# Sensor_Base_Schematic.net
KiCad netlist of a schematic drawn in Altium Designer
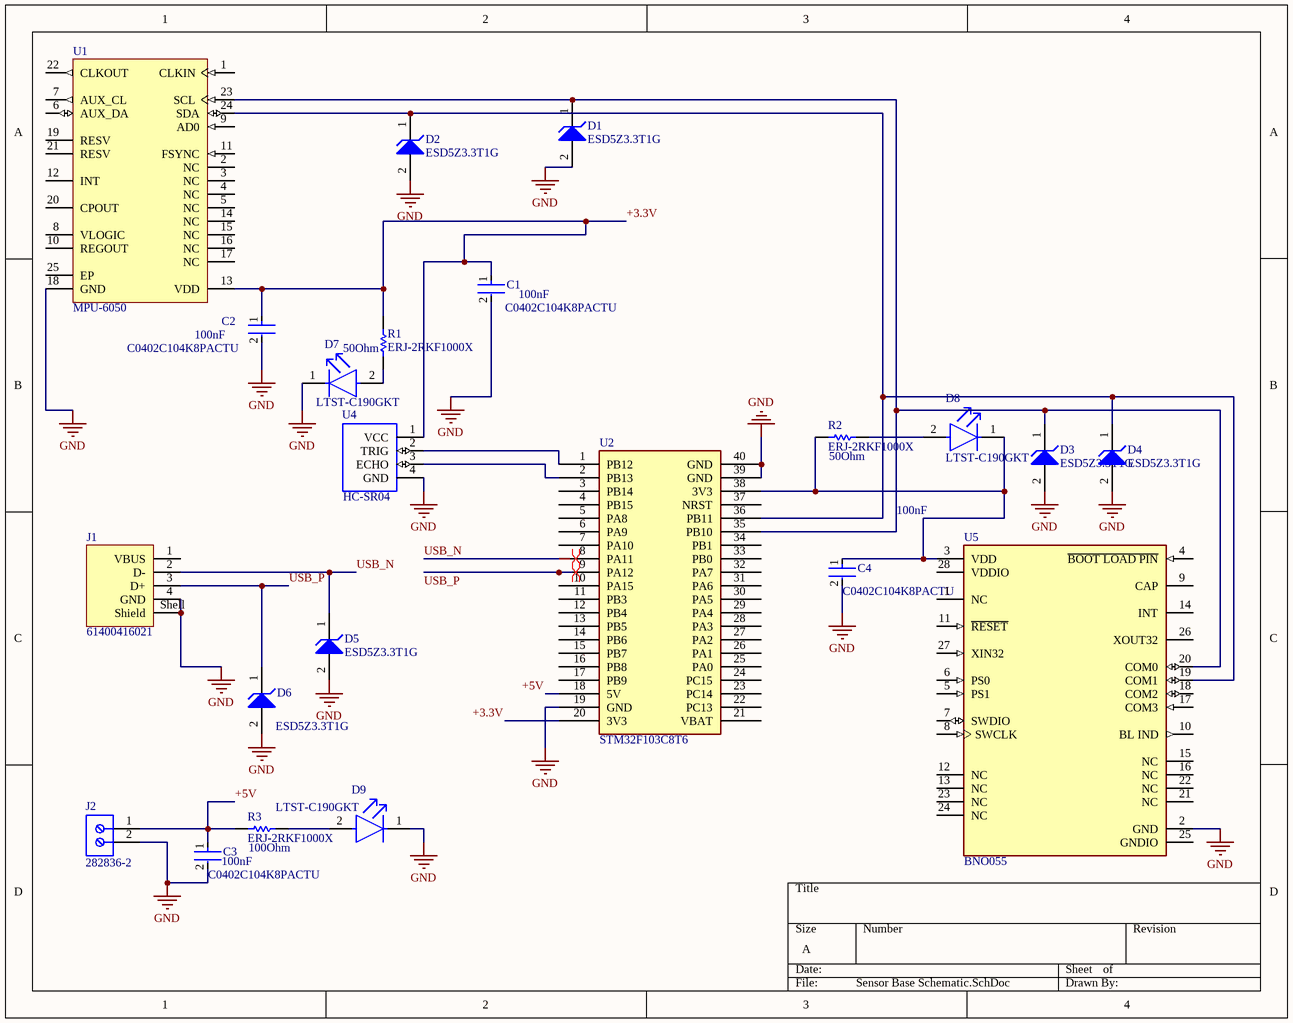
[diagram p0: Sensor Base Schematic.SchDoc]

(export (version "E")
  (design (tool "Eeschema 10.0.6"))
  (components
    (comp (ref "C1")
      (value "C0402C104K8PACTU")
      (footprint "FP-C0402-BB-MFG")
      (description "CAP CER 0.1UF 10V X5R 0402")
      (fields (field (name "MANUFACTURER") "Kemet") (field (name "TOLERANCE") "0.1"))
      (libsource (lib "Altium Content Vault") (part "b4654b650e69147ec39a6b967a45e02"))
    )
    (comp (ref "C2")
      (value "C0402C104K8PACTU")
      (footprint "FP-C0402-BB-MFG")
      (description "CAP CER 0.1UF 10V X5R 0402")
      (fields (field (name "MANUFACTURER") "Kemet") (field (name "TOLERANCE") "0.1"))
      (libsource (lib "Altium Content Vault") (part "b4654b650e69147ec39a6b967a45e02"))
    )
    (comp (ref "C3")
      (value "C0402C104K8PACTU")
      (footprint "FP-C0402-BB-MFG")
      (description "CAP CER 0.1UF 10V X5R 0402")
      (fields (field (name "MANUFACTURER") "Kemet") (field (name "TOLERANCE") "0.1"))
      (libsource (lib "Altium Content Vault") (part "b4654b650e69147ec39a6b967a45e02"))
    )
    (comp (ref "C4")
      (value "C0402C104K8PACTU")
      (footprint "FP-C0402-BB-MFG")
      (description "CAP CER 0.1UF 10V X5R 0402")
      (fields (field (name "MANUFACTURER") "Kemet") (field (name "TOLERANCE") "0.1"))
      (libsource (lib "Altium Content Vault") (part "b4654b650e69147ec39a6b967a45e02"))
    )
    (comp (ref "D1")
      (value "ESD5Z3.3T1G")
      (footprint "ONSC-SOD-523-2-502-01_V")
      (fields (field (name "MANUFACTURER") "On Semiconductor"))
      (libsource (lib "Altium Content Vault") (part "ONSC-K1A2-2"))
    )
    (comp (ref "D2")
      (value "ESD5Z3.3T1G")
      (footprint "ONSC-SOD-523-2-502-01_V")
      (fields (field (name "MANUFACTURER") "On Semiconductor"))
      (libsource (lib "Altium Content Vault") (part "ONSC-K1A2-2"))
    )
    (comp (ref "D3")
      (value "ESD5Z3.3T1G")
      (footprint "ONSC-SOD-523-2-502-01_V")
      (fields (field (name "MANUFACTURER") "On Semiconductor"))
      (libsource (lib "Altium Content Vault") (part "ONSC-K1A2-2"))
    )
    (comp (ref "D4")
      (value "ESD5Z3.3T1G")
      (footprint "ONSC-SOD-523-2-502-01_V")
      (fields (field (name "MANUFACTURER") "On Semiconductor"))
      (libsource (lib "Altium Content Vault") (part "ONSC-K1A2-2"))
    )
    (comp (ref "D5")
      (value "ESD5Z3.3T1G")
      (footprint "ONSC-SOD-523-2-502-01_V")
      (fields (field (name "MANUFACTURER") "On Semiconductor"))
      (libsource (lib "Altium Content Vault") (part "ONSC-K1A2-2"))
    )
    (comp (ref "D6")
      (value "ESD5Z3.3T1G")
      (footprint "ONSC-SOD-523-2-502-01_V")
      (fields (field (name "MANUFACTURER") "On Semiconductor"))
      (libsource (lib "Altium Content Vault") (part "ONSC-K1A2-2"))
    )
    (comp (ref "D7")
      (value "LTST-C190GKT")
      (footprint "FP-LTST-C190GKT-MFG")
      (description "LED GREEN CLEAR CHIP SMD")
      (fields (field (name "VOLTAGE") "2V"))
      (libsource (lib "Altium Content Vault") (part "8706943c75ba83719d021d2fdc84c58"))
    )
    (comp (ref "D8")
      (value "LTST-C190GKT")
      (footprint "FP-LTST-C190GKT-MFG")
      (description "LED GREEN CLEAR CHIP SMD")
      (fields (field (name "VOLTAGE") "2V"))
      (libsource (lib "Altium Content Vault") (part "8706943c75ba83719d021d2fdc84c58"))
    )
    (comp (ref "D9")
      (value "LTST-C190GKT")
      (footprint "FP-LTST-C190GKT-MFG")
      (description "LED GREEN CLEAR CHIP SMD")
      (fields (field (name "VOLTAGE") "2V"))
      (libsource (lib "Altium Content Vault") (part "8706943c75ba83719d021d2fdc84c58"))
    )
    (comp (ref "J1")
      (value "61400416021")
      (footprint "61400416021")
      (libsource (lib "Altium Content Vault") (part "USB 2.0_Type A_Receptacle_1 Port"))
    )
    (comp (ref "J2")
      (value "282836-2")
      (footprint "TECO-282836-2_V")
      (description "Female Header, Pitch 5 mm, 1 x 2 Position, Height 10 mm, Tail Length 3.5 mm, Rohs, Bulk")
      (fields (field (name "VOLTAGE") "300V") (field (name "MANUFACTURER") "TE Connectivity"))
      (libsource (lib "Altium Content Vault") (part "CN-1P-F-TB2"))
    )
    (comp (ref "R1")
      (value "ERJ-2RKF1000X")
      (footprint "RESC1005X40X25LL05T05")
      (description "Chip Resistor, 100 Ohm, +/- 1%, 100 mW, -55 to 155 degC, 0402 (1005 Metric), RoHS, Tape and Reel")
      (fields (field (name "MANUFACTURER") "Basic Passives") (field (name "TOLERANCE") "1%"))
      (libsource (lib "Altium Content Vault") (part "RES-2"))
    )
    (comp (ref "R2")
      (value "ERJ-2RKF1000X")
      (footprint "RESC1005X40X25LL05T05")
      (description "Chip Resistor, 100 Ohm, +/- 1%, 100 mW, -55 to 155 degC, 0402 (1005 Metric), RoHS, Tape and Reel")
      (fields (field (name "MANUFACTURER") "Basic Passives") (field (name "TOLERANCE") "1%"))
      (libsource (lib "Altium Content Vault") (part "RES-2"))
    )
    (comp (ref "R3")
      (value "ERJ-2RKF1000X")
      (footprint "RESC1005X40X25LL05T05")
      (description "Chip Resistor, 100 Ohm, +/- 1%, 100 mW, -55 to 155 degC, 0402 (1005 Metric), RoHS, Tape and Reel")
      (fields (field (name "MANUFACTURER") "Basic Passives") (field (name "TOLERANCE") "1%"))
      (libsource (lib "Altium Content Vault") (part "RES-2"))
    )
    (comp (ref "U1")
      (value "MPU-6050")
      (footprint "IS-QFN-24_V")
      (fields (field (name "MANUFACTURER") "InvenSense"))
      (libsource (lib "Altium Content Vault") (part "IS-MPU-6050-QFN-24"))
    )
    (comp (ref "U2")
      (value "STM32F103C8T6")
      (footprint "Stm32 BluePill")
      (description "Designed By @Alixahedi")
      (libsource (lib "Stm32 Blue Pill") (part "BluePill"))
    )
    (comp (ref "U4")
      (value "HC-SR04")
      (footprint "XCVR_HC-SR04")
      (description "Ultrasonic Sensor Module")
      (libsource (lib "HC-SR04") (part "HC-SR04"))
    )
    (comp (ref "U5")
      (value "BNO055")
      (footprint "FP-BNO055-MFG")
      (description "IMU ACCEL/GYRO/MAG I2C 28LGA")
      (libsource (lib "Altium Content Vault") (part "ba837af00a0b6167256f888b31462b1"))
    )
  )
  (nets
    (net (code "1") (name "/+3.3V") (class "Default")
      (node (ref "C1") (pin "1") (pinfunction "1_1") (pintype "passive"))
      (node (ref "C2") (pin "1") (pinfunction "1_1") (pintype "passive"))
      (node (ref "R1") (pin "2") (pinfunction "2_2") (pintype "passive"))
      (node (ref "U1") (pin "13") (pinfunction "VDD_13") (pintype "power_in"))
      (node (ref "U2") (pin "20") (pinfunction "3V3_20") (pintype "passive"))
      (node (ref "U4") (pin "1") (pinfunction "VCC_1") (pintype "power_in"))
    )
    (net (code "2") (name "/+5V") (class "Default")
      (node (ref "C3") (pin "1") (pinfunction "1_1") (pintype "passive"))
      (node (ref "J2") (pin "1") (pinfunction "1_1") (pintype "passive"))
      (node (ref "R3") (pin "1") (pinfunction "1_1") (pintype "passive"))
      (node (ref "U2") (pin "18") (pinfunction "5V_18") (pintype "passive"))
    )
    (net (code "3") (name "/USB_N") (class "Default")
      (node (ref "D5") (pin "1") (pinfunction "K_1") (pintype "passive"))
      (node (ref "J1") (pin "2") (pinfunction "D-_2") (pintype "passive"))
      (node (ref "U2") (pin "8") (pinfunction "PA11_8") (pintype "passive"))
    )
    (net (code "4") (name "/USB_P") (class "Default")
      (node (ref "D6") (pin "1") (pinfunction "K_1") (pintype "passive"))
      (node (ref "J1") (pin "3") (pinfunction "D+_3") (pintype "passive"))
      (node (ref "U2") (pin "9") (pinfunction "PA12_9") (pintype "passive"))
    )
    (net (code "5") (name "GND") (class "Default")
      (node (ref "C1") (pin "2") (pinfunction "2_2") (pintype "passive"))
      (node (ref "C2") (pin "2") (pinfunction "2_2") (pintype "passive"))
      (node (ref "C3") (pin "2") (pinfunction "2_2") (pintype "passive"))
      (node (ref "C4") (pin "2") (pinfunction "2_2") (pintype "passive"))
      (node (ref "D1") (pin "2") (pinfunction "A_2") (pintype "passive"))
      (node (ref "D2") (pin "2") (pinfunction "A_2") (pintype "passive"))
      (node (ref "D3") (pin "2") (pinfunction "A_2") (pintype "passive"))
      (node (ref "D4") (pin "2") (pinfunction "A_2") (pintype "passive"))
      (node (ref "D5") (pin "2") (pinfunction "A_2") (pintype "passive"))
      (node (ref "D6") (pin "2") (pinfunction "A_2") (pintype "passive"))
      (node (ref "D7") (pin "1") (pinfunction "C_1") (pintype "passive"))
      (node (ref "D9") (pin "1") (pinfunction "C_1") (pintype "passive"))
      (node (ref "J1") (pin "4") (pinfunction "GND_4") (pintype "passive"))
      (node (ref "J1") (pin "Shell") (pinfunction "Shield_Shell") (pintype "passive"))
      (node (ref "J2") (pin "2") (pinfunction "2_2") (pintype "passive"))
      (node (ref "U1") (pin "18") (pinfunction "GND_18") (pintype "power_in"))
      (node (ref "U2") (pin "19") (pinfunction "GND_19") (pintype "passive"))
      (node (ref "U2") (pin "39") (pinfunction "GND_39") (pintype "passive"))
      (node (ref "U2") (pin "40") (pinfunction "GND_40") (pintype "passive"))
      (node (ref "U4") (pin "4") (pinfunction "GND_4") (pintype "power_in"))
      (node (ref "U5") (pin "2") (pinfunction "GND_2") (pintype "power_in"))
    )
    (net (code "6") (name "Net-(D1-K)") (class "Default")
      (node (ref "D1") (pin "1") (pinfunction "K_1") (pintype "passive"))
      (node (ref "D3") (pin "1") (pinfunction "K_1") (pintype "passive"))
      (node (ref "U1") (pin "23") (pinfunction "SCL_23") (pintype "input"))
      (node (ref "U2") (pin "35") (pinfunction "PB10_35") (pintype "passive"))
      (node (ref "U5") (pin "20") (pinfunction "COM0_20") (pintype "bidirectional"))
    )
    (net (code "7") (name "Net-(D2-K)") (class "Default")
      (node (ref "D2") (pin "1") (pinfunction "K_1") (pintype "passive"))
      (node (ref "D4") (pin "1") (pinfunction "K_1") (pintype "passive"))
      (node (ref "U1") (pin "24") (pinfunction "SDA_24") (pintype "bidirectional"))
      (node (ref "U2") (pin "36") (pinfunction "PB11_36") (pintype "passive"))
      (node (ref "U5") (pin "19") (pinfunction "COM1_19") (pintype "bidirectional"))
    )
    (net (code "8") (name "Net-(D7-A)") (class "Default")
      (node (ref "D7") (pin "2") (pinfunction "A_2") (pintype "passive"))
      (node (ref "R1") (pin "1") (pinfunction "1_1") (pintype "passive"))
    )
    (net (code "9") (name "Net-(D8-A)") (class "Default")
      (node (ref "D8") (pin "2") (pinfunction "A_2") (pintype "passive"))
      (node (ref "R2") (pin "2") (pinfunction "2_2") (pintype "passive"))
    )
    (net (code "10") (name "Net-(D8-C)") (class "Default")
      (node (ref "C4") (pin "1") (pinfunction "1_1") (pintype "passive"))
      (node (ref "D8") (pin "1") (pinfunction "C_1") (pintype "passive"))
      (node (ref "R2") (pin "1") (pinfunction "1_1") (pintype "passive"))
      (node (ref "U2") (pin "38") (pinfunction "3V3_38") (pintype "passive"))
      (node (ref "U5") (pin "3") (pinfunction "VDD_3") (pintype "power_in"))
    )
    (net (code "11") (name "Net-(D9-A)") (class "Default")
      (node (ref "D9") (pin "2") (pinfunction "A_2") (pintype "passive"))
      (node (ref "R3") (pin "2") (pinfunction "2_2") (pintype "passive"))
    )
    (net (code "12") (name "Net-(U2-PB12)") (class "Default")
      (node (ref "U2") (pin "1") (pinfunction "PB12_1") (pintype "passive"))
      (node (ref "U4") (pin "2") (pinfunction "TRIG_2") (pintype "bidirectional"))
    )
    (net (code "13") (name "Net-(U2-PB13)") (class "Default")
      (node (ref "U2") (pin "2") (pinfunction "PB13_2") (pintype "passive"))
      (node (ref "U4") (pin "3") (pinfunction "ECHO_3") (pintype "bidirectional"))
    )
    (net (code "14") (name "unconnected-(J1-VBUS-Pad1)") (class "Default")
      (node (ref "J1") (pin "1") (pinfunction "VBUS_1") (pintype "passive"))
    )
    (net (code "15") (name "unconnected-(U1-AD0-Pad9)") (class "Default")
      (node (ref "U1") (pin "9") (pinfunction "AD0_9") (pintype "input"))
    )
    (net (code "16") (name "unconnected-(U1-AUX_CL-Pad7)") (class "Default")
      (node (ref "U1") (pin "7") (pinfunction "AUX_CL_7") (pintype "output"))
    )
    (net (code "17") (name "unconnected-(U1-AUX_DA-Pad6)") (class "Default")
      (node (ref "U1") (pin "6") (pinfunction "AUX_DA_6") (pintype "bidirectional"))
    )
    (net (code "18") (name "unconnected-(U1-CLKIN-Pad1)") (class "Default")
      (node (ref "U1") (pin "1") (pinfunction "CLKIN_1") (pintype "input"))
    )
    (net (code "19") (name "unconnected-(U1-CLKOUT-Pad22)") (class "Default")
      (node (ref "U1") (pin "22") (pinfunction "CLKOUT_22") (pintype "output"))
    )
    (net (code "20") (name "unconnected-(U1-CPOUT-Pad20)") (class "Default")
      (node (ref "U1") (pin "20") (pinfunction "CPOUT_20") (pintype "passive"))
    )
    (net (code "21") (name "unconnected-(U1-EP-Pad25)") (class "Default")
      (node (ref "U1") (pin "25") (pinfunction "EP_25") (pintype "power_in"))
    )
    (net (code "22") (name "unconnected-(U1-FSYNC-Pad11)") (class "Default")
      (node (ref "U1") (pin "11") (pinfunction "FSYNC_11") (pintype "input"))
    )
    (net (code "23") (name "unconnected-(U1-INT-Pad12)") (class "Default")
      (node (ref "U1") (pin "12") (pinfunction "INT_12") (pintype "open_collector"))
    )
    (net (code "24") (name "unconnected-(U1-NC-Pad2)") (class "Default")
      (node (ref "U1") (pin "2") (pinfunction "NC_2") (pintype "passive"))
    )
    (net (code "25") (name "unconnected-(U1-NC-Pad3)") (class "Default")
      (node (ref "U1") (pin "3") (pinfunction "NC_3") (pintype "passive"))
    )
    (net (code "26") (name "unconnected-(U1-NC-Pad4)") (class "Default")
      (node (ref "U1") (pin "4") (pinfunction "NC_4") (pintype "passive"))
    )
    (net (code "27") (name "unconnected-(U1-NC-Pad5)") (class "Default")
      (node (ref "U1") (pin "5") (pinfunction "NC_5") (pintype "passive"))
    )
    (net (code "28") (name "unconnected-(U1-NC-Pad14)") (class "Default")
      (node (ref "U1") (pin "14") (pinfunction "NC_14") (pintype "passive"))
    )
    (net (code "29") (name "unconnected-(U1-NC-Pad15)") (class "Default")
      (node (ref "U1") (pin "15") (pinfunction "NC_15") (pintype "passive"))
    )
    (net (code "30") (name "unconnected-(U1-NC-Pad16)") (class "Default")
      (node (ref "U1") (pin "16") (pinfunction "NC_16") (pintype "passive"))
    )
    (net (code "31") (name "unconnected-(U1-NC-Pad17)") (class "Default")
      (node (ref "U1") (pin "17") (pinfunction "NC_17") (pintype "passive"))
    )
    (net (code "32") (name "unconnected-(U1-REGOUT-Pad10)") (class "Default")
      (node (ref "U1") (pin "10") (pinfunction "REGOUT_10") (pintype "passive"))
    )
    (net (code "33") (name "unconnected-(U1-RESV-Pad19)") (class "Default")
      (node (ref "U1") (pin "19") (pinfunction "RESV_19") (pintype "passive"))
    )
    (net (code "34") (name "unconnected-(U1-RESV-Pad21)") (class "Default")
      (node (ref "U1") (pin "21") (pinfunction "RESV_21") (pintype "passive"))
    )
    (net (code "35") (name "unconnected-(U1-VLOGIC-Pad8)") (class "Default")
      (node (ref "U1") (pin "8") (pinfunction "VLOGIC_8") (pintype "power_in"))
    )
    (net (code "36") (name "unconnected-(U2-NRST-Pad37)") (class "Default")
      (node (ref "U2") (pin "37") (pinfunction "NRST_37") (pintype "passive"))
    )
    (net (code "37") (name "unconnected-(U2-PA0-Pad25)") (class "Default")
      (node (ref "U2") (pin "25") (pinfunction "PA0_25") (pintype "passive"))
    )
    (net (code "38") (name "unconnected-(U2-PA1-Pad26)") (class "Default")
      (node (ref "U2") (pin "26") (pinfunction "PA1_26") (pintype "passive"))
    )
    (net (code "39") (name "unconnected-(U2-PA2-Pad27)") (class "Default")
      (node (ref "U2") (pin "27") (pinfunction "PA2_27") (pintype "passive"))
    )
    (net (code "40") (name "unconnected-(U2-PA3-Pad28)") (class "Default")
      (node (ref "U2") (pin "28") (pinfunction "PA3_28") (pintype "passive"))
    )
    (net (code "41") (name "unconnected-(U2-PA4-Pad29)") (class "Default")
      (node (ref "U2") (pin "29") (pinfunction "PA4_29") (pintype "passive"))
    )
    (net (code "42") (name "unconnected-(U2-PA5-Pad30)") (class "Default")
      (node (ref "U2") (pin "30") (pinfunction "PA5_30") (pintype "passive"))
    )
    (net (code "43") (name "unconnected-(U2-PA6-Pad31)") (class "Default")
      (node (ref "U2") (pin "31") (pinfunction "PA6_31") (pintype "passive"))
    )
    (net (code "44") (name "unconnected-(U2-PA7-Pad32)") (class "Default")
      (node (ref "U2") (pin "32") (pinfunction "PA7_32") (pintype "passive"))
    )
    (net (code "45") (name "unconnected-(U2-PA8-Pad5)") (class "Default")
      (node (ref "U2") (pin "5") (pinfunction "PA8_5") (pintype "passive"))
    )
    (net (code "46") (name "unconnected-(U2-PA9-Pad6)") (class "Default")
      (node (ref "U2") (pin "6") (pinfunction "PA9_6") (pintype "passive"))
    )
    (net (code "47") (name "unconnected-(U2-PA10-Pad7)") (class "Default")
      (node (ref "U2") (pin "7") (pinfunction "PA10_7") (pintype "passive"))
    )
    (net (code "48") (name "unconnected-(U2-PA15-Pad10)") (class "Default")
      (node (ref "U2") (pin "10") (pinfunction "PA15_10") (pintype "passive"))
    )
    (net (code "49") (name "unconnected-(U2-PB0-Pad33)") (class "Default")
      (node (ref "U2") (pin "33") (pinfunction "PB0_33") (pintype "passive"))
    )
    (net (code "50") (name "unconnected-(U2-PB1-Pad34)") (class "Default")
      (node (ref "U2") (pin "34") (pinfunction "PB1_34") (pintype "passive"))
    )
    (net (code "51") (name "unconnected-(U2-PB3-Pad11)") (class "Default")
      (node (ref "U2") (pin "11") (pinfunction "PB3_11") (pintype "passive"))
    )
    (net (code "52") (name "unconnected-(U2-PB4-Pad12)") (class "Default")
      (node (ref "U2") (pin "12") (pinfunction "PB4_12") (pintype "passive"))
    )
    (net (code "53") (name "unconnected-(U2-PB5-Pad13)") (class "Default")
      (node (ref "U2") (pin "13") (pinfunction "PB5_13") (pintype "passive"))
    )
    (net (code "54") (name "unconnected-(U2-PB6-Pad14)") (class "Default")
      (node (ref "U2") (pin "14") (pinfunction "PB6_14") (pintype "passive"))
    )
    (net (code "55") (name "unconnected-(U2-PB7-Pad15)") (class "Default")
      (node (ref "U2") (pin "15") (pinfunction "PB7_15") (pintype "passive"))
    )
    (net (code "56") (name "unconnected-(U2-PB8-Pad16)") (class "Default")
      (node (ref "U2") (pin "16") (pinfunction "PB8_16") (pintype "passive"))
    )
    (net (code "57") (name "unconnected-(U2-PB9-Pad17)") (class "Default")
      (node (ref "U2") (pin "17") (pinfunction "PB9_17") (pintype "passive"))
    )
    (net (code "58") (name "unconnected-(U2-PB14-Pad3)") (class "Default")
      (node (ref "U2") (pin "3") (pinfunction "PB14_3") (pintype "passive"))
    )
    (net (code "59") (name "unconnected-(U2-PB15-Pad4)") (class "Default")
      (node (ref "U2") (pin "4") (pinfunction "PB15_4") (pintype "passive"))
    )
    (net (code "60") (name "unconnected-(U2-PC13-Pad22)") (class "Default")
      (node (ref "U2") (pin "22") (pinfunction "PC13_22") (pintype "passive"))
    )
    (net (code "61") (name "unconnected-(U2-PC14-Pad23)") (class "Default")
      (node (ref "U2") (pin "23") (pinfunction "PC14_23") (pintype "passive"))
    )
    (net (code "62") (name "unconnected-(U2-PC15-Pad24)") (class "Default")
      (node (ref "U2") (pin "24") (pinfunction "PC15_24") (pintype "passive"))
    )
    (net (code "63") (name "unconnected-(U2-VBAT-Pad21)") (class "Default")
      (node (ref "U2") (pin "21") (pinfunction "VBAT_21") (pintype "passive"))
    )
    (net (code "64") (name "unconnected-(U5-BL_IND-Pad10)") (class "Default")
      (node (ref "U5") (pin "10") (pinfunction "BL_IND_10") (pintype "output"))
    )
    (net (code "65") (name "unconnected-(U5-CAP-Pad9)") (class "Default")
      (node (ref "U5") (pin "9") (pinfunction "CAP_9") (pintype "passive"))
    )
    (net (code "66") (name "unconnected-(U5-COM2-Pad18)") (class "Default")
      (node (ref "U5") (pin "18") (pinfunction "COM2_18") (pintype "bidirectional"))
    )
    (net (code "67") (name "unconnected-(U5-COM3-Pad17)") (class "Default")
      (node (ref "U5") (pin "17") (pinfunction "COM3_17") (pintype "input"))
    )
    (net (code "68") (name "unconnected-(U5-GNDIO-Pad25)") (class "Default")
      (node (ref "U5") (pin "25") (pinfunction "GNDIO_25") (pintype "power_in"))
    )
    (net (code "69") (name "unconnected-(U5-INT-Pad14)") (class "Default")
      (node (ref "U5") (pin "14") (pinfunction "INT_14") (pintype "passive"))
    )
    (net (code "70") (name "unconnected-(U5-NC-Pad1)") (class "Default")
      (node (ref "U5") (pin "1") (pinfunction "NC_1") (pintype "passive"))
    )
    (net (code "71") (name "unconnected-(U5-NC-Pad12)") (class "Default")
      (node (ref "U5") (pin "12") (pinfunction "NC_12") (pintype "passive"))
    )
    (net (code "72") (name "unconnected-(U5-NC-Pad13)") (class "Default")
      (node (ref "U5") (pin "13") (pinfunction "NC_13") (pintype "passive"))
    )
    (net (code "73") (name "unconnected-(U5-NC-Pad15)") (class "Default")
      (node (ref "U5") (pin "15") (pinfunction "NC_15") (pintype "passive"))
    )
    (net (code "74") (name "unconnected-(U5-NC-Pad16)") (class "Default")
      (node (ref "U5") (pin "16") (pinfunction "NC_16") (pintype "passive"))
    )
    (net (code "75") (name "unconnected-(U5-NC-Pad21)") (class "Default")
      (node (ref "U5") (pin "21") (pinfunction "NC_21") (pintype "passive"))
    )
    (net (code "76") (name "unconnected-(U5-NC-Pad22)") (class "Default")
      (node (ref "U5") (pin "22") (pinfunction "NC_22") (pintype "passive"))
    )
    (net (code "77") (name "unconnected-(U5-NC-Pad23)") (class "Default")
      (node (ref "U5") (pin "23") (pinfunction "NC_23") (pintype "passive"))
    )
    (net (code "78") (name "unconnected-(U5-NC-Pad24)") (class "Default")
      (node (ref "U5") (pin "24") (pinfunction "NC_24") (pintype "passive"))
    )
    (net (code "79") (name "unconnected-(U5-PS0-Pad6)") (class "Default")
      (node (ref "U5") (pin "6") (pinfunction "PS0_6") (pintype "input"))
    )
    (net (code "80") (name "unconnected-(U5-PS1-Pad5)") (class "Default")
      (node (ref "U5") (pin "5") (pinfunction "PS1_5") (pintype "input"))
    )
    (net (code "81") (name "unconnected-(U5-SWCLK-Pad8)") (class "Default")
      (node (ref "U5") (pin "8") (pinfunction "SWCLK_8") (pintype "input"))
    )
    (net (code "82") (name "unconnected-(U5-SWDIO-Pad7)") (class "Default")
      (node (ref "U5") (pin "7") (pinfunction "SWDIO_7") (pintype "bidirectional"))
    )
    (net (code "83") (name "unconnected-(U5-VDDIO-Pad28)") (class "Default")
      (node (ref "U5") (pin "28") (pinfunction "VDDIO_28") (pintype "power_in"))
    )
    (net (code "84") (name "unconnected-(U5-XIN32-Pad27)") (class "Default")
      (node (ref "U5") (pin "27") (pinfunction "XIN32_27") (pintype "input"))
    )
    (net (code "85") (name "unconnected-(U5-XOUT32-Pad26)") (class "Default")
      (node (ref "U5") (pin "26") (pinfunction "XOUT32_26") (pintype "passive"))
    )
    (net (code "86") (name "unconnected-(U5-~{BOOT_LOAD_PIN}-Pad4)") (class "Default")
      (node (ref "U5") (pin "4") (pinfunction "~{BOOT_LOAD_PIN}_4") (pintype "input"))
    )
    (net (code "87") (name "unconnected-(U5-~{RESET}-Pad11)") (class "Default")
      (node (ref "U5") (pin "11") (pinfunction "~{RESET}_11") (pintype "input"))
    )
  )
)
